# Sheet1.net
KiCad netlist of a schematic drawn in Altium Designer
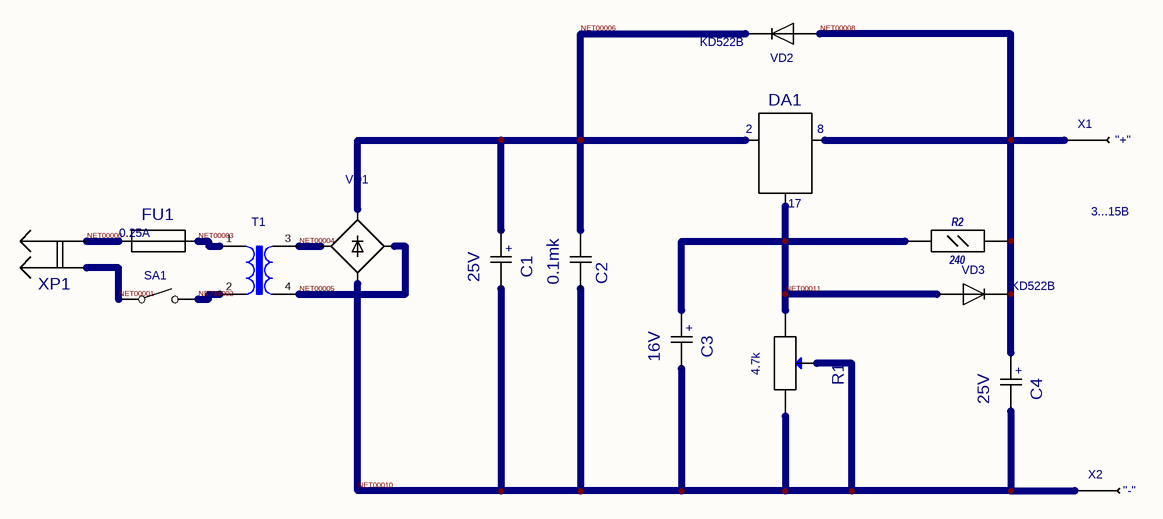
[diagram p0: Sheet1.SCHDOC]

(export (version "E")
  (design (tool "Eeschema 10.0.6"))
  (components
    (comp (ref "C1")
      (value "25V")
      (footprint "CAP2")
      (description "CAP2")
      (libsource (lib "*") (part "CAP2"))
    )
    (comp (ref "C2")
      (value "0.1mk")
      (footprint "CAP1")
      (description "CAP1")
      (libsource (lib "*") (part "CAP1"))
    )
    (comp (ref "C3")
      (value "16V")
      (footprint "CAP2")
      (description "CAP2")
      (libsource (lib "*") (part "CAP2"))
    )
    (comp (ref "C4")
      (value "25V")
      (footprint "CAP2")
      (description "CAP2")
      (libsource (lib "*") (part "CAP2"))
    )
    (comp (ref "DA1") (value "КР1158ЕН5") (footprint "KT26-3") (libsource (lib "*") (part "КР1158ЕН5")))
    (comp (ref "FU1")
      (value "0.25A")
      (footprint "VP1-1")
      (description "ВП1-1")
      (libsource (lib "*") (part "ВП1-1"))
    )
    (comp (ref "R1")
      (value "4.7k")
      (footprint "RESVAR")
      (description "RESVAR")
      (libsource (lib "*") (part "RESVAR"))
    )
    (comp (ref "R2")
      (value "240")
      (footprint "МЛТ(0.125)")
      (description "МЛТ(0.125)")
      (libsource (lib "*") (part "МЛТ(0.125)"))
    )
    (comp (ref "SA1") (value "TURN") (footprint "TRN") (libsource (lib "*") (part "TURN")))
    (comp (ref "T1") (value "TR") (footprint "TR") (libsource (lib "*") (part "TR")))
    (comp (ref "VD1")
      (value "DIODEBRIDGE")
      (footprint "DIODEBRIDGE")
      (libsource (lib "*") (part "DIODEBRIDGE"))
    )
    (comp (ref "VD2")
      (value "KD522B")
      (footprint "DIODE")
      (description "DIODE")
      (libsource (lib "*") (part "DIODE"))
    )
    (comp (ref "VD3")
      (value "KD522B")
      (footprint "DIODE")
      (description "DIODE")
      (libsource (lib "*") (part "DIODE"))
    )
    (comp (ref "X1") (value "CONN1X") (footprint "CONN1X") (libsource (lib "*") (part "CONN1X")))
    (comp (ref "X2") (value "CONN1X") (footprint "CONN1X") (libsource (lib "*") (part "CONN1X")))
    (comp (ref "XP1") (value "2XR") (footprint "2XR") (libsource (lib "*") (part "2XR")))
  )
  (nets
    (net (code "1") (name "/NET00000") (class "Default")
      (node (ref "FU1") (pin "1") (pinfunction "I/O1_1") (pintype "passive"))
      (node (ref "XP1") (pin "2") (pinfunction "I/O2_2") (pintype "passive"))
    )
    (net (code "2") (name "/NET00001") (class "Default")
      (node (ref "SA1") (pin "1") (pintype "passive"))
      (node (ref "XP1") (pin "1") (pinfunction "I/O1_1") (pintype "passive"))
    )
    (net (code "3") (name "/NET00002") (class "Default")
      (node (ref "SA1") (pin "2") (pintype "passive"))
      (node (ref "T1") (pin "2") (pintype "passive"))
    )
    (net (code "4") (name "/NET00003") (class "Default")
      (node (ref "FU1") (pin "2") (pinfunction "I/O2_2") (pintype "passive"))
      (node (ref "T1") (pin "1") (pintype "passive"))
    )
    (net (code "5") (name "/NET00004") (class "Default")
      (node (ref "T1") (pin "3") (pintype "passive"))
      (node (ref "VD1") (pin "1") (pinfunction "1_1") (pintype "passive"))
    )
    (net (code "6") (name "/NET00005") (class "Default")
      (node (ref "T1") (pin "4") (pintype "passive"))
      (node (ref "VD1") (pin "2") (pinfunction "2_2") (pintype "passive"))
    )
    (net (code "7") (name "/NET00006") (class "Default")
      (node (ref "C1") (pin "1") (pinfunction "1_1") (pintype "passive"))
      (node (ref "C2") (pin "1") (pintype "passive"))
      (node (ref "DA1") (pin "1") (pinfunction "IN0_1") (pintype "passive"))
      (node (ref "VD1") (pin "4") (pinfunction "4_4") (pintype "passive"))
      (node (ref "VD2") (pin "2") (pinfunction "2_2") (pintype "passive"))
    )
    (net (code "8") (name "/NET00008") (class "Default")
      (node (ref "C4") (pin "1") (pinfunction "1_1") (pintype "passive"))
      (node (ref "DA1") (pin "3") (pinfunction "OUT0_3") (pintype "passive"))
      (node (ref "R2") (pin "2") (pinfunction "2_2") (pintype "passive"))
      (node (ref "VD2") (pin "1") (pinfunction "1_1") (pintype "passive"))
      (node (ref "VD3") (pin "2") (pinfunction "2_2") (pintype "passive"))
      (node (ref "X1") (pin "1") (pinfunction "1_1") (pintype "passive"))
    )
    (net (code "9") (name "/NET00010") (class "Default")
      (node (ref "C1") (pin "2") (pinfunction "2_2") (pintype "passive"))
      (node (ref "C2") (pin "2") (pintype "passive"))
      (node (ref "C3") (pin "2") (pinfunction "2_2") (pintype "passive"))
      (node (ref "C4") (pin "2") (pinfunction "2_2") (pintype "passive"))
      (node (ref "R1") (pin "2") (pinfunction "2_2") (pintype "passive"))
      (node (ref "R1") (pin "3") (pinfunction "3_3") (pintype "passive"))
      (node (ref "VD1") (pin "3") (pinfunction "3_3") (pintype "passive"))
      (node (ref "X2") (pin "1") (pinfunction "1_1") (pintype "passive"))
    )
    (net (code "10") (name "/NET00011") (class "Default")
      (node (ref "C3") (pin "1") (pinfunction "1_1") (pintype "passive"))
      (node (ref "DA1") (pin "2") (pinfunction "GND0_2") (pintype "passive"))
      (node (ref "R1") (pin "1") (pinfunction "1_1") (pintype "passive"))
      (node (ref "R2") (pin "1") (pinfunction "1_1") (pintype "passive"))
      (node (ref "VD3") (pin "1") (pinfunction "1_1") (pintype "passive"))
    )
    (net (code "11") (name "unconnected-(FU1-Pad3)") (class "Default")
      (node (ref "FU1") (pin "3") (pintype "passive"))
    )
    (net (code "12") (name "unconnected-(FU1-Pad4)") (class "Default")
      (node (ref "FU1") (pin "4") (pintype "passive"))
    )
  )
)
